# Adafruit_0_56_7-Segment_QT.net
KiCad netlist of a schematic drawn in EAGLE
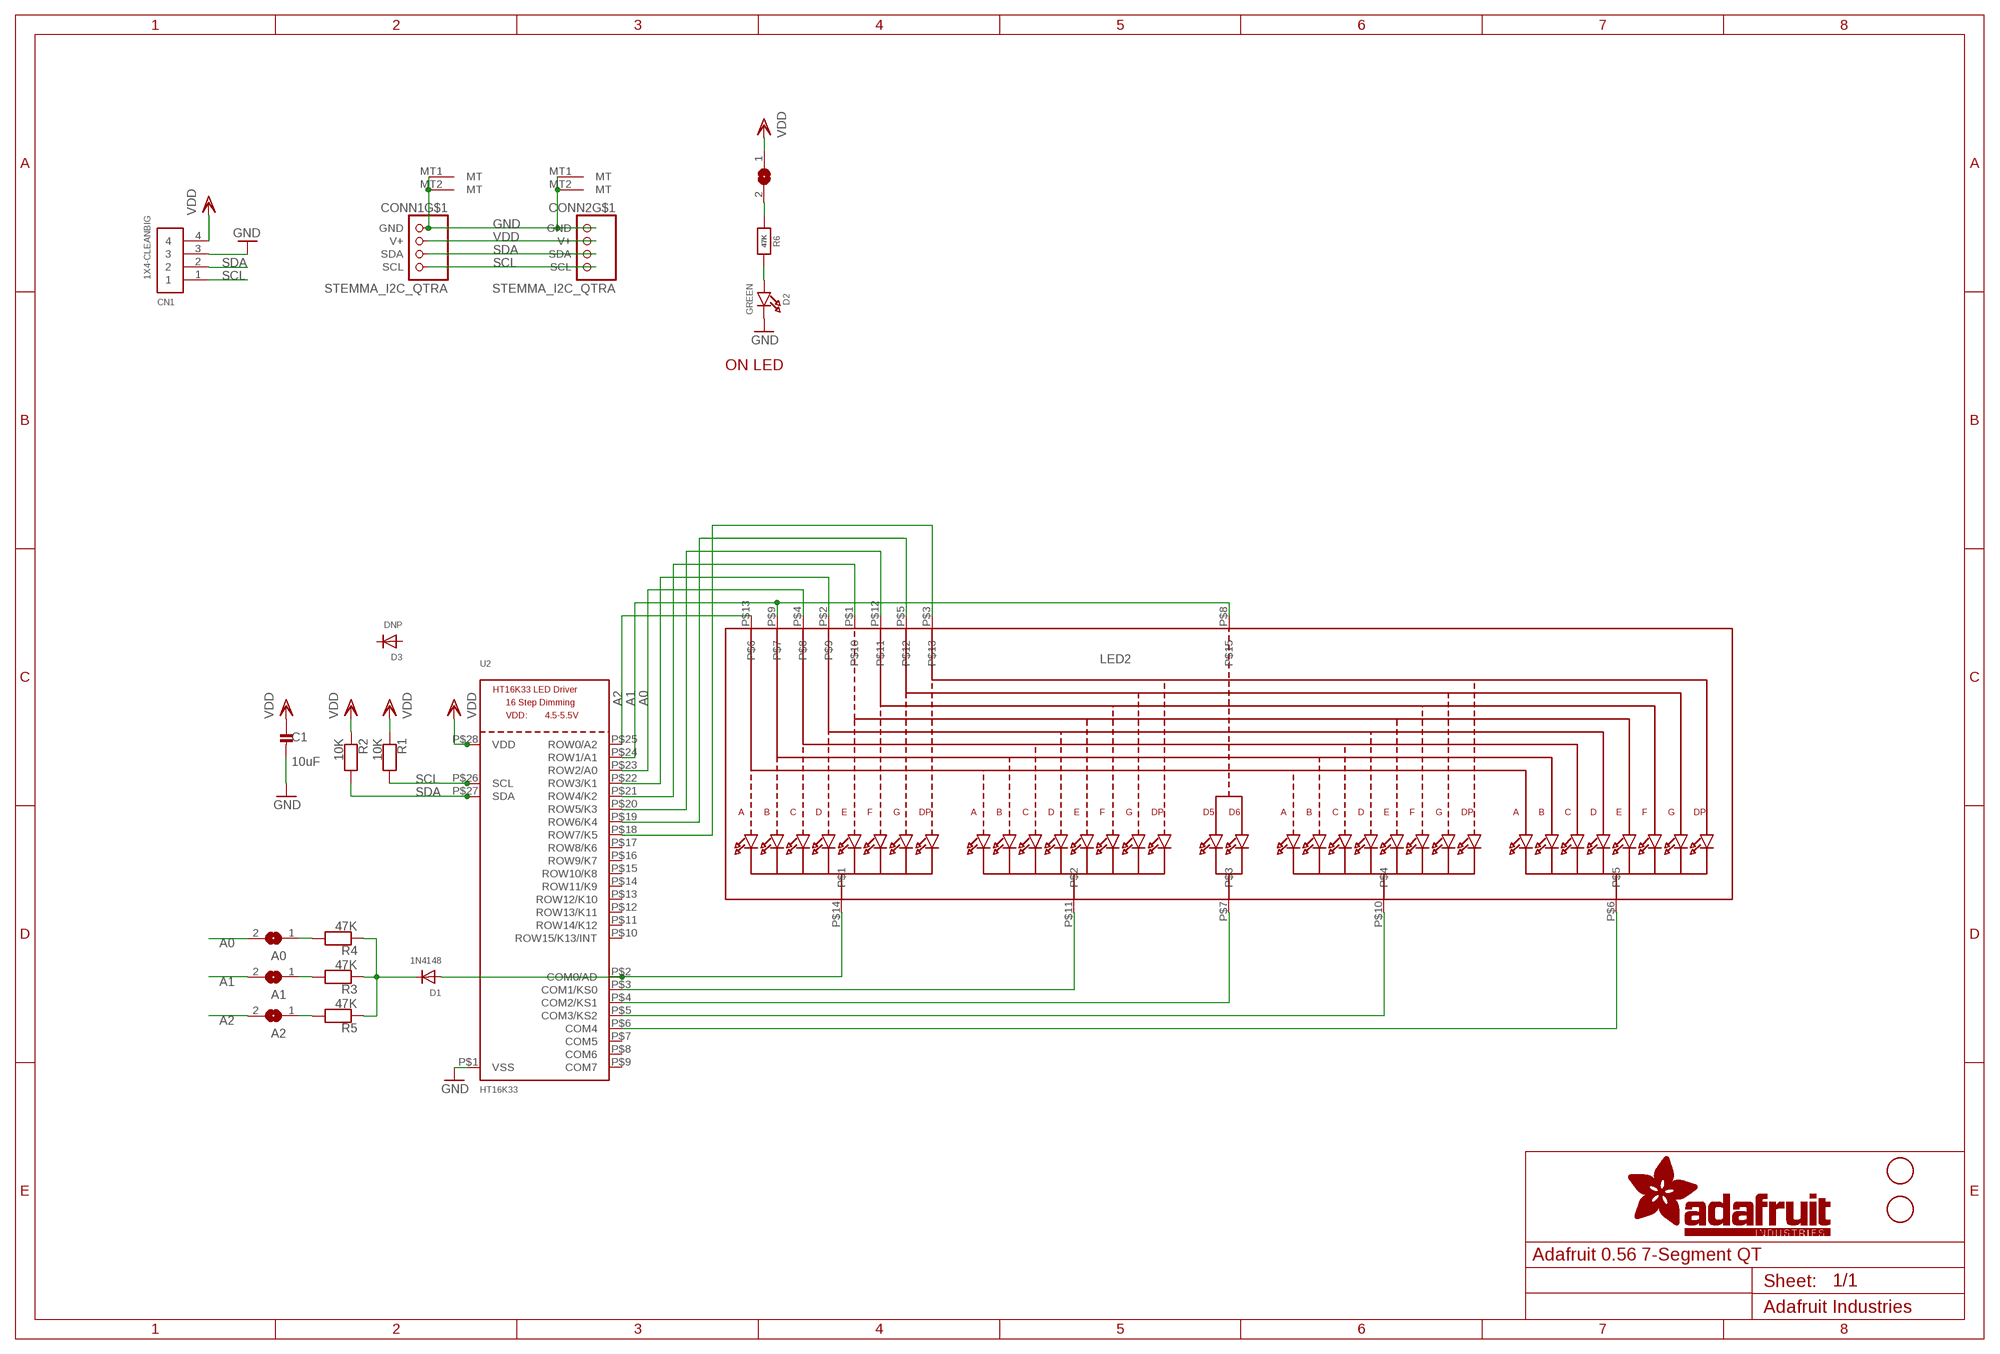
[diagram p0: schematic, sheet 1]

(export (version "E")
  (design (tool "Eeschema 10.0.6"))
  (components
    (comp (ref "A0")
      (value "SOLDERJUMPER")
      (footprint "eagle-import:SOLDERJUMPER_ARROW_NOPASTE")
      (libsource (lib "eagle-import") (part "SOLDERJUMPER"))
    )
    (comp (ref "A1")
      (value "SOLDERJUMPER")
      (footprint "eagle-import:SOLDERJUMPER_ARROW_NOPASTE")
      (libsource (lib "eagle-import") (part "SOLDERJUMPER"))
    )
    (comp (ref "A2")
      (value "SOLDERJUMPER")
      (footprint "eagle-import:SOLDERJUMPER_ARROW_NOPASTE")
      (libsource (lib "eagle-import") (part "SOLDERJUMPER"))
    )
    (comp (ref "C1")
      (value "10uF")
      (footprint "eagle-import:0805_10MGAP")
      (libsource (lib "eagle-import") (part "CAP_CERAMIC0805_10MGAP"))
    )
    (comp (ref "CN1")
      (value "1X4-CLEANBIG")
      (footprint "eagle-import:1X04-CLEANBIG")
      (libsource (lib "eagle-import") (part "1X4-CLEANBIG"))
    )
    (comp (ref "CONN1")
      (value "STEMMA_I2C_QTRA")
      (footprint "eagle-import:JST_SH4_RA")
      (libsource (lib "eagle-import") (part "STEMMA_I2C_QTRA"))
    )
    (comp (ref "CONN2")
      (value "STEMMA_I2C_QTRA")
      (footprint "eagle-import:JST_SH4_RA")
      (libsource (lib "eagle-import") (part "STEMMA_I2C_QTRA"))
    )
    (comp (ref "D1")
      (value "1N4148")
      (footprint "eagle-import:SOD-323F")
      (libsource (lib "eagle-import") (part "DIODESOD-323F"))
    )
    (comp (ref "D2")
      (value "GREEN")
      (footprint "eagle-import:CHIPLED_0603_NOOUTLINE")
      (libsource (lib "eagle-import") (part "LED0603_NOOUTLINE"))
    )
    (comp (ref "D3")
      (value "DNP")
      (footprint "eagle-import:SOD-323F")
      (libsource (lib "eagle-import") (part "DIODESOD-323F"))
    )
    (comp (ref "LED2")
      (value "DISP_SEGMENT_4DIGIT_BL-Q56C43")
      (footprint "eagle-import:SEGMENT-BL-Q56C43")
      (libsource (lib "eagle-import") (part "DISP_SEGMENT_4DIGIT_BL-Q56C43"))
    )
    (comp (ref "LEDJMP")
      (value "SOLDERJUMPERCLOSED")
      (footprint "eagle-import:SOLDERJUMPER_CLOSEDWIRE")
      (libsource (lib "eagle-import") (part "SOLDERJUMPERCLOSED"))
    )
    (comp (ref "R1")
      (value "10K")
      (footprint "eagle-import:0603-NO")
      (libsource (lib "eagle-import") (part "RESISTOR_0603_NOOUT"))
    )
    (comp (ref "R2")
      (value "10K")
      (footprint "eagle-import:0603-NO")
      (libsource (lib "eagle-import") (part "RESISTOR_0603_NOOUT"))
    )
    (comp (ref "R3")
      (value "47K")
      (footprint "eagle-import:0603-NO")
      (libsource (lib "eagle-import") (part "RESISTOR_0603_NOOUT"))
    )
    (comp (ref "R4")
      (value "47K")
      (footprint "eagle-import:0603-NO")
      (libsource (lib "eagle-import") (part "RESISTOR_0603_NOOUT"))
    )
    (comp (ref "R5")
      (value "47K")
      (footprint "eagle-import:0603-NO")
      (libsource (lib "eagle-import") (part "RESISTOR_0603_NOOUT"))
    )
    (comp (ref "R6")
      (value "47K")
      (footprint "eagle-import:0603-NO")
      (libsource (lib "eagle-import") (part "RESISTOR_0603_NOOUT"))
    )
    (comp (ref "U$1")
      (value "FIDUCIAL")
      (footprint "eagle-import:FIDUCIAL_1MM")
      (libsource (lib "eagle-import") (part "FIDUCIAL"))
    )
    (comp (ref "U$2")
      (value "FIDUCIAL")
      (footprint "eagle-import:FIDUCIAL_1MM")
      (libsource (lib "eagle-import") (part "FIDUCIAL"))
    )
    (comp (ref "U2")
      (value "HT16K33")
      (footprint "eagle-import:SOP28_300MIL_SKINNY")
      (libsource (lib "eagle-import") (part "HT16K33_SOP28_SKINNY"))
    )
  )
  (nets
    (net (code "1") (name "/A0") (class "Default")
      (node (ref "A0") (pin "2") (pinfunction "2_2") (pintype "passive"))
      (node (ref "LED2") (pin "P$4") (pinfunction "P$8_P$4") (pintype "bidirectional"))
      (node (ref "U2") (pin "P$23") (pinfunction "ROW2/A0_P$23") (pintype "bidirectional"))
    )
    (net (code "2") (name "/A1") (class "Default")
      (node (ref "A1") (pin "2") (pinfunction "2_2") (pintype "passive"))
      (node (ref "LED2") (pin "P$8") (pinfunction "P$15_P$8") (pintype "bidirectional"))
      (node (ref "LED2") (pin "P$9") (pinfunction "P$7_P$9") (pintype "bidirectional"))
      (node (ref "U2") (pin "P$24") (pinfunction "ROW1/A1_P$24") (pintype "bidirectional"))
    )
    (net (code "3") (name "/A2") (class "Default")
      (node (ref "A2") (pin "2") (pinfunction "2_2") (pintype "passive"))
      (node (ref "LED2") (pin "P$13") (pinfunction "P$6_P$13") (pintype "bidirectional"))
      (node (ref "U2") (pin "P$25") (pinfunction "ROW0/A2_P$25") (pintype "bidirectional"))
    )
    (net (code "4") (name "/SCL") (class "Default")
      (node (ref "CN1") (pin "1") (pinfunction "1_1") (pintype "bidirectional"))
      (node (ref "CONN1") (pin "4") (pinfunction "SCL_4") (pintype "passive"))
      (node (ref "CONN2") (pin "4") (pinfunction "SCL_4") (pintype "passive"))
      (node (ref "R1") (pin "2") (pinfunction "2_2") (pintype "passive"))
      (node (ref "U2") (pin "P$26") (pinfunction "SCL_P$26") (pintype "bidirectional"))
    )
    (net (code "5") (name "/SDA") (class "Default")
      (node (ref "CN1") (pin "2") (pinfunction "2_2") (pintype "bidirectional"))
      (node (ref "CONN1") (pin "3") (pinfunction "SDA_3") (pintype "passive"))
      (node (ref "CONN2") (pin "3") (pinfunction "SDA_3") (pintype "passive"))
      (node (ref "R2") (pin "2") (pinfunction "2_2") (pintype "passive"))
      (node (ref "U2") (pin "P$27") (pinfunction "SDA_P$27") (pintype "bidirectional"))
    )
    (net (code "6") (name "GND") (class "Default")
      (node (ref "C1") (pin "2") (pinfunction "2_2") (pintype "passive"))
      (node (ref "CN1") (pin "3") (pinfunction "3_3") (pintype "bidirectional"))
      (node (ref "CONN1") (pin "1") (pinfunction "GND_1") (pintype "passive"))
      (node (ref "CONN1") (pin "MT1") (pinfunction "MT_MT1") (pintype "bidirectional"))
      (node (ref "CONN1") (pin "MT2") (pinfunction "MT_MT2") (pintype "bidirectional"))
      (node (ref "CONN2") (pin "1") (pinfunction "GND_1") (pintype "passive"))
      (node (ref "CONN2") (pin "MT1") (pinfunction "MT_MT1") (pintype "bidirectional"))
      (node (ref "CONN2") (pin "MT2") (pinfunction "MT_MT2") (pintype "bidirectional"))
      (node (ref "D2") (pin "C") (pinfunction "C_C") (pintype "passive"))
      (node (ref "U2") (pin "P$1") (pinfunction "VSS_P$1") (pintype "bidirectional"))
    )
    (net (code "7") (name "Net-(A0-Pad1)") (class "Default")
      (node (ref "A0") (pin "1") (pinfunction "1_1") (pintype "passive"))
      (node (ref "R4") (pin "2") (pinfunction "2_2") (pintype "passive"))
    )
    (net (code "8") (name "Net-(A1-Pad1)") (class "Default")
      (node (ref "A1") (pin "1") (pinfunction "1_1") (pintype "passive"))
      (node (ref "R3") (pin "2") (pinfunction "2_2") (pintype "passive"))
    )
    (net (code "9") (name "Net-(A2-Pad1)") (class "Default")
      (node (ref "A2") (pin "1") (pinfunction "1_1") (pintype "passive"))
      (node (ref "R5") (pin "2") (pinfunction "2_2") (pintype "passive"))
    )
    (net (code "10") (name "Net-(D1-PadC)") (class "Default")
      (node (ref "D1") (pin "C") (pinfunction "C_C") (pintype "passive"))
      (node (ref "R3") (pin "1") (pinfunction "1_1") (pintype "passive"))
      (node (ref "R4") (pin "1") (pinfunction "1_1") (pintype "passive"))
      (node (ref "R5") (pin "1") (pinfunction "1_1") (pintype "passive"))
    )
    (net (code "11") (name "Net-(D2-PadA)") (class "Default")
      (node (ref "D2") (pin "A") (pinfunction "A_A") (pintype "passive"))
      (node (ref "R6") (pin "2") (pinfunction "2_2") (pintype "passive"))
    )
    (net (code "12") (name "Net-(LED2-P$1)") (class "Default")
      (node (ref "D1") (pin "A") (pinfunction "A_A") (pintype "passive"))
      (node (ref "LED2") (pin "P$14") (pinfunction "P$1_P$14") (pintype "bidirectional"))
      (node (ref "U2") (pin "P$2") (pinfunction "COM0/AD_P$2") (pintype "bidirectional"))
    )
    (net (code "13") (name "Net-(LED2-P$2)") (class "Default")
      (node (ref "LED2") (pin "P$11") (pinfunction "P$2_P$11") (pintype "bidirectional"))
      (node (ref "U2") (pin "P$3") (pinfunction "COM1/KS0_P$3") (pintype "bidirectional"))
    )
    (net (code "14") (name "Net-(LED2-P$3)") (class "Default")
      (node (ref "LED2") (pin "P$7") (pinfunction "P$3_P$7") (pintype "bidirectional"))
      (node (ref "U2") (pin "P$4") (pinfunction "COM2/KS1_P$4") (pintype "bidirectional"))
    )
    (net (code "15") (name "Net-(LED2-P$4)") (class "Default")
      (node (ref "LED2") (pin "P$10") (pinfunction "P$4_P$10") (pintype "bidirectional"))
      (node (ref "U2") (pin "P$5") (pinfunction "COM3/KS2_P$5") (pintype "bidirectional"))
    )
    (net (code "16") (name "Net-(LED2-P$5)") (class "Default")
      (node (ref "LED2") (pin "P$6") (pinfunction "P$5_P$6") (pintype "bidirectional"))
      (node (ref "U2") (pin "P$6") (pinfunction "COM4_P$6") (pintype "bidirectional"))
    )
    (net (code "17") (name "Net-(LED2-P$9)") (class "Default")
      (node (ref "LED2") (pin "P$2") (pinfunction "P$9_P$2") (pintype "bidirectional"))
      (node (ref "U2") (pin "P$22") (pinfunction "ROW3/K1_P$22") (pintype "bidirectional"))
    )
    (net (code "18") (name "Net-(LED2-P$10)") (class "Default")
      (node (ref "LED2") (pin "P$1") (pinfunction "P$10_P$1") (pintype "bidirectional"))
      (node (ref "U2") (pin "P$21") (pinfunction "ROW4/K2_P$21") (pintype "bidirectional"))
    )
    (net (code "19") (name "Net-(LED2-P$11)") (class "Default")
      (node (ref "LED2") (pin "P$12") (pinfunction "P$11_P$12") (pintype "bidirectional"))
      (node (ref "U2") (pin "P$20") (pinfunction "ROW5/K3_P$20") (pintype "bidirectional"))
    )
    (net (code "20") (name "Net-(LED2-P$12)") (class "Default")
      (node (ref "LED2") (pin "P$5") (pinfunction "P$12_P$5") (pintype "bidirectional"))
      (node (ref "U2") (pin "P$19") (pinfunction "ROW6/K4_P$19") (pintype "bidirectional"))
    )
    (net (code "21") (name "Net-(LED2-P$13)") (class "Default")
      (node (ref "LED2") (pin "P$3") (pinfunction "P$13_P$3") (pintype "bidirectional"))
      (node (ref "U2") (pin "P$18") (pinfunction "ROW7/K5_P$18") (pintype "bidirectional"))
    )
    (net (code "22") (name "Net-(LEDJMP-Pad2)") (class "Default")
      (node (ref "LEDJMP") (pin "2") (pinfunction "2_2") (pintype "passive"))
      (node (ref "R6") (pin "1") (pinfunction "1_1") (pintype "passive"))
    )
    (net (code "23") (name "VDD") (class "Default")
      (node (ref "C1") (pin "1") (pinfunction "1_1") (pintype "passive"))
      (node (ref "CN1") (pin "4") (pinfunction "4_4") (pintype "bidirectional"))
      (node (ref "CONN1") (pin "2") (pinfunction "V+_2") (pintype "passive"))
      (node (ref "CONN2") (pin "2") (pinfunction "V+_2") (pintype "passive"))
      (node (ref "LEDJMP") (pin "1") (pinfunction "1_1") (pintype "passive"))
      (node (ref "R1") (pin "1") (pinfunction "1_1") (pintype "passive"))
      (node (ref "R2") (pin "1") (pinfunction "1_1") (pintype "passive"))
      (node (ref "U2") (pin "P$28") (pinfunction "VDD_P$28") (pintype "bidirectional"))
    )
    (net (code "24") (name "unconnected-(D3-PadA)") (class "Default")
      (node (ref "D3") (pin "A") (pinfunction "A_A") (pintype "passive"))
    )
    (net (code "25") (name "unconnected-(D3-PadC)") (class "Default")
      (node (ref "D3") (pin "C") (pinfunction "C_C") (pintype "passive"))
    )
    (net (code "26") (name "unconnected-(U2-COM5-PadP$7)") (class "Default")
      (node (ref "U2") (pin "P$7") (pinfunction "COM5_P$7") (pintype "bidirectional"))
    )
    (net (code "27") (name "unconnected-(U2-COM6-PadP$8)") (class "Default")
      (node (ref "U2") (pin "P$8") (pinfunction "COM6_P$8") (pintype "bidirectional"))
    )
    (net (code "28") (name "unconnected-(U2-COM7-PadP$9)") (class "Default")
      (node (ref "U2") (pin "P$9") (pinfunction "COM7_P$9") (pintype "bidirectional"))
    )
    (net (code "29") (name "unconnected-(U2-ROW8{slash}K6-PadP$17)") (class "Default")
      (node (ref "U2") (pin "P$17") (pinfunction "ROW8/K6_P$17") (pintype "bidirectional"))
    )
    (net (code "30") (name "unconnected-(U2-ROW9{slash}K7-PadP$16)") (class "Default")
      (node (ref "U2") (pin "P$16") (pinfunction "ROW9/K7_P$16") (pintype "bidirectional"))
    )
    (net (code "31") (name "unconnected-(U2-ROW10{slash}K8-PadP$15)") (class "Default")
      (node (ref "U2") (pin "P$15") (pinfunction "ROW10/K8_P$15") (pintype "bidirectional"))
    )
    (net (code "32") (name "unconnected-(U2-ROW11{slash}K9-PadP$14)") (class "Default")
      (node (ref "U2") (pin "P$14") (pinfunction "ROW11/K9_P$14") (pintype "bidirectional"))
    )
    (net (code "33") (name "unconnected-(U2-ROW12{slash}K10-PadP$13)") (class "Default")
      (node (ref "U2") (pin "P$13") (pinfunction "ROW12/K10_P$13") (pintype "bidirectional"))
    )
    (net (code "34") (name "unconnected-(U2-ROW13{slash}K11-PadP$12)") (class "Default")
      (node (ref "U2") (pin "P$12") (pinfunction "ROW13/K11_P$12") (pintype "bidirectional"))
    )
    (net (code "35") (name "unconnected-(U2-ROW14{slash}K12-PadP$11)") (class "Default")
      (node (ref "U2") (pin "P$11") (pinfunction "ROW14/K12_P$11") (pintype "bidirectional"))
    )
    (net (code "36") (name "unconnected-(U2-ROW15{slash}K13{slash}INT-PadP$10)") (class "Default")
      (node (ref "U2") (pin "P$10") (pinfunction "ROW15/K13/INT_P$10") (pintype "bidirectional"))
    )
  )
)
